# Processing.net
KiCad netlist of a schematic drawn in Altium Designer
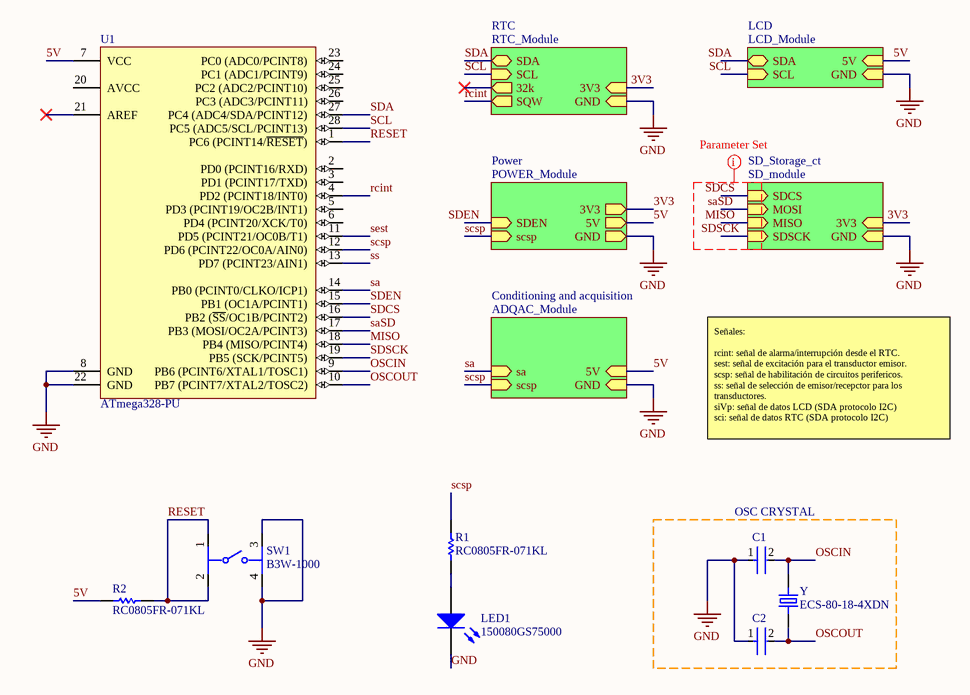
[diagram p0: Processing.SchDoc]

(export (version "E")
  (design (tool "Eeschema 10.0.6"))
  (components
    (comp (ref "C1")
      (value "C0603C200J5GACTU")
      (footprint "FP-C0603C-CF-MFG")
      (description "CAP CER 20PF 50V 5% NP0 0603")
      (fields
        (field (name "MANUFACTURER") "KEMET")
        (field (name "OCTOPART") "https://octopart.com/c0603c200j5gactu-kemet-9138585")
      )
      (libsource (lib "Altium Content Vault") (part "b4654b650e69147ec39a6b967a45e02"))
    )
    (comp (ref "C2")
      (value "C0603C200J5GACTU")
      (footprint "FP-C0603C-CF-MFG")
      (description "CAP CER 20PF 50V 5% NP0 0603")
      (fields
        (field (name "MANUFACTURER") "KEMET")
        (field (name "OCTOPART") "https://octopart.com/c0603c200j5gactu-kemet-9138585")
      )
      (libsource (lib "Altium Content Vault") (part "b4654b650e69147ec39a6b967a45e02"))
    )
    (comp (ref "LED1")
      (value "150080GS75000")
      (footprint "0805_A")
      (description "SMD mono-color Chip LED, WL-SMCW, Green")
      (fields (field (name "MANUFACTURER") "Wuerth Elektronik"))
      (libsource (lib "Altium Content Vault") (part "WE-LED_K1A2-2"))
    )
    (comp (ref "R1")
      (value "RC0805FR-071KL")
      (footprint "RESC2013X60X35ML10T20")
      (description "Chip Resistor, 1 KOhm, +/- 1%, 125 mW, -55 to 155 degC, 0805 (2012 Metric), RoHS, Tape and Reel")
      (fields (field (name "TOLERANCE") "1%") (field (name "MANUFACTURER") "Yageo"))
      (libsource (lib "Altium Content Vault") (part "RES-2"))
    )
    (comp (ref "R2")
      (value "RC0805FR-071KL")
      (footprint "RESC2013X60X35ML10T20")
      (description "Chip Resistor, 1 KOhm, +/- 1%, 125 mW, -55 to 155 degC, 0805 (2012 Metric), RoHS, Tape and Reel")
      (fields (field (name "TOLERANCE") "1%") (field (name "MANUFACTURER") "Yageo"))
      (libsource (lib "Altium Content Vault") (part "RES-2"))
    )
    (comp (ref "SW1")
      (value "B3W-1000")
      (footprint "FP-B3W-1000-MFG")
      (description "SWITCH TACTILE SPST-NO 0.05A 24V")
      (libsource (lib "Altium Content Vault") (part "b8895f3f4cefb76e1819d2863dba89b"))
    )
    (comp (ref "U1")
      (value "ATmega328-PU")
      (footprint "28P3")
      (libsource (lib "Altium Content Vault") (part "MC-8B-ATM48-IL28"))
    )
    (comp (ref "Y")
      (value "ECS-80-18-4XDN")
      (footprint "XTAL_ECS-80-18-4XDN")
      (description "8MHz Â±30ppm Crystal 18pF 80 Ohms HC-49/US")
      (fields (field (name "DIGI-KEY_PART_NUMBER") "X1115-ND") (field (name "MF") "ECS Inc."))
      (libsource (lib "ECS-80-18-4XDN") (part "ECS-80-18-4XDN"))
    )
  )
  (nets
    (net (code "2") (name "/5V") (class "Default")
      (node (ref "R2") (pin "1") (pinfunction "1_1") (pintype "passive"))
      (node (ref "U1") (pin "7") (pinfunction "VCC_7") (pintype "power_in"))
    )
    (net (code "4") (name "/MISO") (class "Default")
      (node (ref "U1") (pin "18") (pinfunction "PB4_(MISO/PCINT4)_18") (pintype "bidirectional"))
    )
    (net (code "5") (name "/OSCIN") (class "Default")
      (node (ref "C1") (pin "2") (pinfunction "2_2") (pintype "passive"))
      (node (ref "U1") (pin "9") (pinfunction "PB6_(PCINT6/XTAL1/TOSC1)_9") (pintype "bidirectional"))
      (node (ref "Y") (pin "2") (pinfunction "2_2") (pintype "passive"))
    )
    (net (code "6") (name "/OSCOUT") (class "Default")
      (node (ref "C2") (pin "2") (pinfunction "2_2") (pintype "passive"))
      (node (ref "U1") (pin "10") (pinfunction "PB7_(PCINT7/XTAL2/TOSC2)_10") (pintype "bidirectional"))
      (node (ref "Y") (pin "1") (pinfunction "1_1") (pintype "passive"))
    )
    (net (code "7") (name "/RESET") (class "Default")
      (node (ref "R2") (pin "2") (pinfunction "2_2") (pintype "passive"))
      (node (ref "SW1") (pin "1") (pinfunction "1_1") (pintype "passive"))
      (node (ref "SW1") (pin "2") (pinfunction "2_2") (pintype "passive"))
      (node (ref "U1") (pin "1") (pinfunction "PC6_(PCINT14/~{RESET})_1") (pintype "bidirectional"))
    )
    (net (code "8") (name "/SCL") (class "Default")
      (node (ref "U1") (pin "28") (pinfunction "PC5_(ADC5/SCL/PCINT13)_28") (pintype "bidirectional"))
    )
    (net (code "9") (name "/SDA") (class "Default")
      (node (ref "U1") (pin "27") (pinfunction "PC4_(ADC4/SDA/PCINT12)_27") (pintype "bidirectional"))
    )
    (net (code "10") (name "/SDCS") (class "Default")
      (node (ref "U1") (pin "16") (pinfunction "PB2_(~{SS}/OC1B/PCINT2)_16") (pintype "bidirectional"))
    )
    (net (code "11") (name "/SDEN") (class "Default")
      (node (ref "U1") (pin "15") (pinfunction "PB1_(OC1A/PCINT1)_15") (pintype "bidirectional"))
    )
    (net (code "12") (name "/SDSCK") (class "Default")
      (node (ref "U1") (pin "19") (pinfunction "PB5_(SCK/PCINT5)_19") (pintype "bidirectional"))
    )
    (net (code "13") (name "/rcint") (class "Default")
      (node (ref "U1") (pin "4") (pinfunction "PD2_(PCINT18/INT0)_4") (pintype "bidirectional"))
    )
    (net (code "14") (name "/sa") (class "Default")
      (node (ref "U1") (pin "14") (pinfunction "PB0_(PCINT0/CLKO/ICP1)_14") (pintype "bidirectional"))
    )
    (net (code "15") (name "/saSD") (class "Default")
      (node (ref "U1") (pin "17") (pinfunction "PB3_(MOSI/OC2A/PCINT3)_17") (pintype "bidirectional"))
    )
    (net (code "16") (name "/scsp") (class "Default")
      (node (ref "R1") (pin "1") (pinfunction "1_1") (pintype "passive"))
      (node (ref "U1") (pin "12") (pinfunction "PD6_(PCINT22/OC0A/AIN0)_12") (pintype "bidirectional"))
    )
    (net (code "17") (name "/sest") (class "Default")
      (node (ref "U1") (pin "11") (pinfunction "PD5_(PCINT21/OC0B/T1)_11") (pintype "bidirectional"))
    )
    (net (code "18") (name "/ss") (class "Default")
      (node (ref "U1") (pin "13") (pinfunction "PD7_(PCINT23/AIN1)_13") (pintype "bidirectional"))
    )
    (net (code "19") (name "GND") (class "Default")
      (node (ref "C1") (pin "1") (pinfunction "1_1") (pintype "passive"))
      (node (ref "C2") (pin "1") (pinfunction "1_1") (pintype "passive"))
      (node (ref "LED1") (pin "1") (pinfunction "K_1") (pintype "passive"))
      (node (ref "SW1") (pin "3") (pinfunction "3_3") (pintype "passive"))
      (node (ref "SW1") (pin "4") (pinfunction "4_4") (pintype "passive"))
      (node (ref "U1") (pin "22") (pinfunction "GND_22") (pintype "power_in"))
      (node (ref "U1") (pin "8") (pinfunction "GND_8") (pintype "power_in"))
    )
    (net (code "20") (name "Net-(LED1-A)") (class "Default")
      (node (ref "LED1") (pin "2") (pinfunction "A_2") (pintype "passive"))
      (node (ref "R1") (pin "2") (pinfunction "2_2") (pintype "passive"))
    )
    (net (code "21") (name "unconnected-(U1-AREF-Pad21)") (class "Default")
      (node (ref "U1") (pin "21") (pinfunction "AREF_21") (pintype "power_in+no_connect"))
    )
    (net (code "22") (name "unconnected-(U1-AVCC-Pad20)") (class "Default")
      (node (ref "U1") (pin "20") (pinfunction "AVCC_20") (pintype "power_in"))
    )
    (net (code "23") (name "unconnected-(U1-PC0_(ADC0{slash}PCINT8)-Pad23)") (class "Default")
      (node (ref "U1") (pin "23") (pinfunction "PC0_(ADC0/PCINT8)_23") (pintype "bidirectional"))
    )
    (net (code "24") (name "unconnected-(U1-PC1_(ADC1{slash}PCINT9)-Pad24)") (class "Default")
      (node (ref "U1") (pin "24") (pinfunction "PC1_(ADC1/PCINT9)_24") (pintype "bidirectional"))
    )
    (net (code "25") (name "unconnected-(U1-PC2_(ADC2{slash}PCINT10)-Pad25)") (class "Default")
      (node (ref "U1") (pin "25") (pinfunction "PC2_(ADC2/PCINT10)_25") (pintype "bidirectional"))
    )
    (net (code "26") (name "unconnected-(U1-PC3_(ADC3{slash}PCINT11)-Pad26)") (class "Default")
      (node (ref "U1") (pin "26") (pinfunction "PC3_(ADC3/PCINT11)_26") (pintype "bidirectional"))
    )
    (net (code "27") (name "unconnected-(U1-PD0_(PCINT16{slash}RXD)-Pad2)") (class "Default")
      (node (ref "U1") (pin "2") (pinfunction "PD0_(PCINT16/RXD)_2") (pintype "bidirectional"))
    )
    (net (code "28") (name "unconnected-(U1-PD1_(PCINT17{slash}TXD)-Pad3)") (class "Default")
      (node (ref "U1") (pin "3") (pinfunction "PD1_(PCINT17/TXD)_3") (pintype "bidirectional"))
    )
    (net (code "29") (name "unconnected-(U1-PD3_(PCINT19{slash}OC2B{slash}INT1)-Pad5)") (class "Default")
      (node (ref "U1") (pin "5") (pinfunction "PD3_(PCINT19/OC2B/INT1)_5") (pintype "bidirectional"))
    )
    (net (code "30") (name "unconnected-(U1-PD4_(PCINT20{slash}XCK{slash}T0)-Pad6)") (class "Default")
      (node (ref "U1") (pin "6") (pinfunction "PD4_(PCINT20/XCK/T0)_6") (pintype "bidirectional"))
    )
  )
)
